# sensor.net
KiCad netlist of a schematic drawn in EAGLE
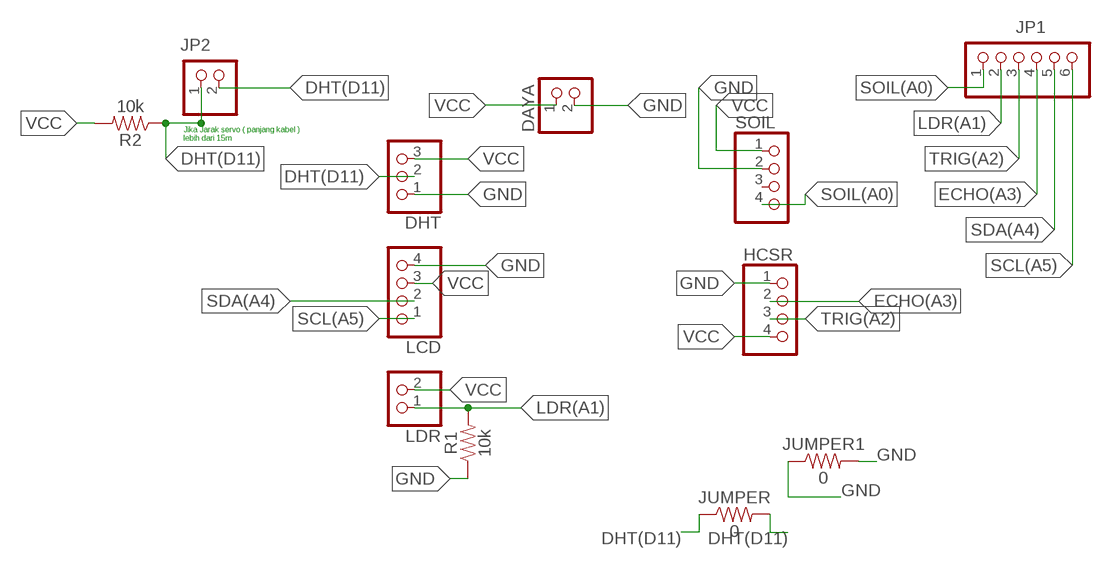
[diagram p0: schematic, sheet 1]

(export (version "E")
  (design (tool "Eeschema 10.0.6"))
  (components
    (comp (ref "DAYA")
      (value "PINHD-1X2")
      (footprint "eagle-import:1X02")
      (libsource (lib "eagle-import") (part "PINHD-1X2"))
    )
    (comp (ref "DHT")
      (value "PINHD-1X3")
      (footprint "eagle-import:1X03")
      (libsource (lib "eagle-import") (part "PINHD-1X3"))
    )
    (comp (ref "HCSR")
      (value "PINHD-1X4")
      (footprint "eagle-import:1X04")
      (libsource (lib "eagle-import") (part "PINHD-1X4"))
    )
    (comp (ref "JP1")
      (value "PINHD-1X6")
      (footprint "eagle-import:1X06")
      (libsource (lib "eagle-import") (part "PINHD-1X6"))
    )
    (comp (ref "JP2")
      (value "PINHD-1X2")
      (footprint "eagle-import:1X02")
      (libsource (lib "eagle-import") (part "PINHD-1X2"))
    )
    (comp (ref "JUMPER")
      (value "0")
      (footprint "eagle-import:AXIAL-0.3")
      (libsource (lib "eagle-import") (part "1KOHM-HORIZ-1/4W-1%"))
    )
    (comp (ref "JUMPER1")
      (value "0")
      (footprint "eagle-import:AXIAL-0.3")
      (libsource (lib "eagle-import") (part "1KOHM-HORIZ-1/4W-1%"))
    )
    (comp (ref "LCD")
      (value "PINHD-1X4")
      (footprint "eagle-import:1X04")
      (libsource (lib "eagle-import") (part "PINHD-1X4"))
    )
    (comp (ref "LDR")
      (value "PINHD-1X2")
      (footprint "eagle-import:1X02")
      (libsource (lib "eagle-import") (part "PINHD-1X2"))
    )
    (comp (ref "R1")
      (value "10k")
      (footprint "eagle-import:AXIAL-0.3")
      (libsource (lib "eagle-import") (part "10KOHM-HORIZ-1/4W-5%"))
    )
    (comp (ref "R2")
      (value "10k")
      (footprint "eagle-import:AXIAL-0.3")
      (libsource (lib "eagle-import") (part "10KOHM-HORIZ-1/4W-5%"))
    )
    (comp (ref "SOIL")
      (value "PINHD-1X4")
      (footprint "eagle-import:1X04")
      (libsource (lib "eagle-import") (part "PINHD-1X4"))
    )
  )
  (nets
    (net (code "1") (name "DHT(D11)") (class "Default")
      (node (ref "DHT") (pin "2") (pinfunction "2_2") (pintype "passive"))
      (node (ref "JP2") (pin "1") (pinfunction "1_1") (pintype "passive"))
      (node (ref "JP2") (pin "2") (pinfunction "2_2") (pintype "passive"))
      (node (ref "JUMPER") (pin "P$1") (pinfunction "1_P$1") (pintype "passive"))
      (node (ref "JUMPER") (pin "P$2") (pinfunction "2_P$2") (pintype "passive"))
      (node (ref "R2") (pin "P$1") (pinfunction "1_P$1") (pintype "passive"))
    )
    (net (code "2") (name "ECHO(A3)") (class "Default")
      (node (ref "HCSR") (pin "2") (pinfunction "2_2") (pintype "passive"))
      (node (ref "JP1") (pin "4") (pinfunction "4_4") (pintype "passive"))
    )
    (net (code "3") (name "GND") (class "Default")
      (node (ref "DAYA") (pin "2") (pinfunction "2_2") (pintype "passive"))
      (node (ref "DHT") (pin "1") (pinfunction "1_1") (pintype "passive"))
      (node (ref "HCSR") (pin "1") (pinfunction "1_1") (pintype "passive"))
      (node (ref "JUMPER1") (pin "P$1") (pinfunction "1_P$1") (pintype "passive"))
      (node (ref "JUMPER1") (pin "P$2") (pinfunction "2_P$2") (pintype "passive"))
      (node (ref "LCD") (pin "4") (pinfunction "4_4") (pintype "passive"))
      (node (ref "R1") (pin "P$1") (pinfunction "1_P$1") (pintype "passive"))
      (node (ref "SOIL") (pin "2") (pinfunction "2_2") (pintype "passive"))
    )
    (net (code "4") (name "LDR(A1)") (class "Default")
      (node (ref "JP1") (pin "2") (pinfunction "2_2") (pintype "passive"))
      (node (ref "LDR") (pin "1") (pinfunction "1_1") (pintype "passive"))
      (node (ref "R1") (pin "P$2") (pinfunction "2_P$2") (pintype "passive"))
    )
    (net (code "5") (name "SCL(A5)") (class "Default")
      (node (ref "JP1") (pin "6") (pinfunction "6_6") (pintype "passive"))
      (node (ref "LCD") (pin "1") (pinfunction "1_1") (pintype "passive"))
    )
    (net (code "6") (name "SDA(A4)") (class "Default")
      (node (ref "JP1") (pin "5") (pinfunction "5_5") (pintype "passive"))
      (node (ref "LCD") (pin "2") (pinfunction "2_2") (pintype "passive"))
    )
    (net (code "7") (name "SOIL(A0)") (class "Default")
      (node (ref "JP1") (pin "1") (pinfunction "1_1") (pintype "passive"))
      (node (ref "SOIL") (pin "4") (pinfunction "4_4") (pintype "passive"))
    )
    (net (code "8") (name "TRIG(A2)") (class "Default")
      (node (ref "HCSR") (pin "3") (pinfunction "3_3") (pintype "passive"))
      (node (ref "JP1") (pin "3") (pinfunction "3_3") (pintype "passive"))
    )
    (net (code "9") (name "VCC") (class "Default")
      (node (ref "DAYA") (pin "1") (pinfunction "1_1") (pintype "passive"))
      (node (ref "DHT") (pin "3") (pinfunction "3_3") (pintype "passive"))
      (node (ref "HCSR") (pin "4") (pinfunction "4_4") (pintype "passive"))
      (node (ref "LCD") (pin "3") (pinfunction "3_3") (pintype "passive"))
      (node (ref "LDR") (pin "2") (pinfunction "2_2") (pintype "passive"))
      (node (ref "R2") (pin "P$2") (pinfunction "2_P$2") (pintype "passive"))
      (node (ref "SOIL") (pin "1") (pinfunction "1_1") (pintype "passive"))
    )
    (net (code "10") (name "unconnected-(SOIL-Pad3)") (class "Default")
      (node (ref "SOIL") (pin "3") (pinfunction "3_3") (pintype "passive"))
    )
  )
)
